# ovenboard.net
KiCad netlist of a schematic drawn in EAGLE
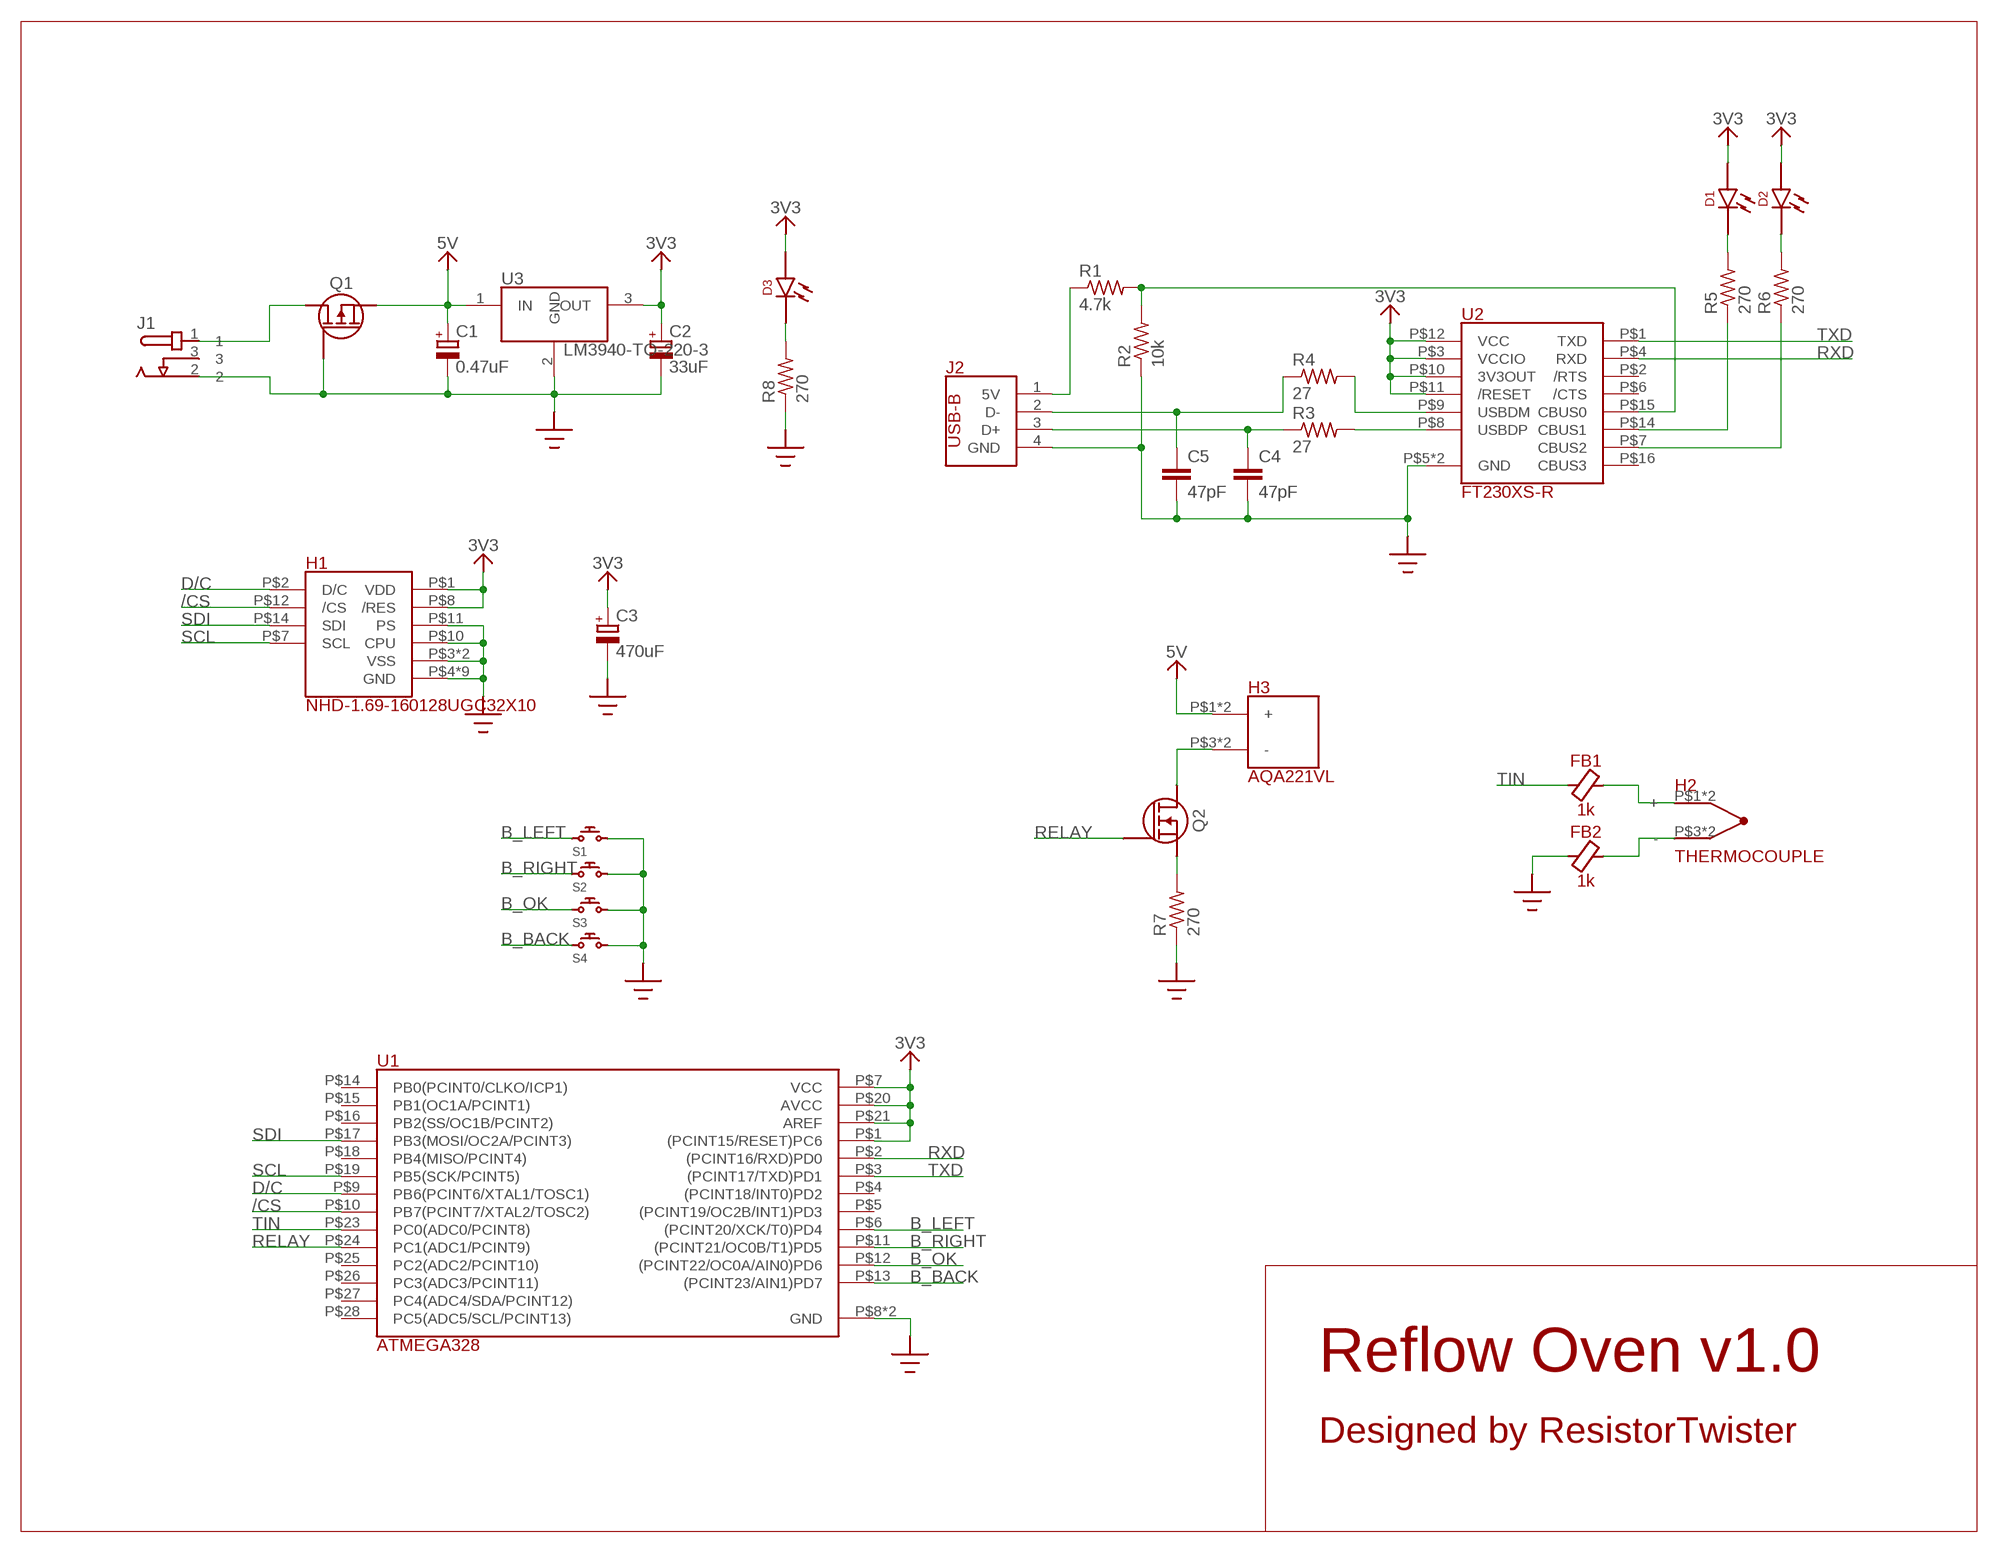
[diagram p0: schematic, sheet 1]

(export (version "E")
  (design (tool "Eeschema 10.0.6"))
  (components
    (comp (ref "C1")
      (value "0.47uF")
      (footprint "eagle-import:E5-5")
      (libsource (lib "eagle-import") (part "CPOL-EUE5-5"))
    )
    (comp (ref "C2")
      (value "33uF")
      (footprint "eagle-import:E5-5")
      (libsource (lib "eagle-import") (part "CPOL-EUE5-5"))
    )
    (comp (ref "C3")
      (value "470uF")
      (footprint "eagle-import:E5-5")
      (libsource (lib "eagle-import") (part "CPOL-EUE5-5"))
    )
    (comp (ref "C4")
      (value "47pF")
      (footprint "eagle-import:C050-024X044")
      (libsource (lib "eagle-import") (part "C-EU050-024X044"))
    )
    (comp (ref "C5")
      (value "47pF")
      (footprint "eagle-import:C050-024X044")
      (libsource (lib "eagle-import") (part "C-EU050-024X044"))
    )
    (comp (ref "D1")
      (value "LED-5")
      (footprint "eagle-import:LED5")
      (libsource (lib "eagle-import") (part "LED-5"))
    )
    (comp (ref "D2")
      (value "LED-5")
      (footprint "eagle-import:LED5")
      (libsource (lib "eagle-import") (part "LED-5"))
    )
    (comp (ref "D3")
      (value "LED-5")
      (footprint "eagle-import:LED5")
      (libsource (lib "eagle-import") (part "LED-5"))
    )
    (comp (ref "FB1")
      (value "1k")
      (footprint "eagle-import:0603")
      (libsource (lib "eagle-import") (part "FERRITE-0603"))
    )
    (comp (ref "FB2")
      (value "1k")
      (footprint "eagle-import:0603")
      (libsource (lib "eagle-import") (part "FERRITE-0603"))
    )
    (comp (ref "H1")
      (value "NHD-1.69-160128UGC32X10")
      (footprint "eagle-import:2X10HEADER0.1")
      (libsource (lib "eagle-import") (part "NHD-1.69-160128UGC32X10"))
    )
    (comp (ref "H2")
      (value "THERMOCOUPLE")
      (footprint "eagle-import:2TERMINAL")
      (libsource (lib "eagle-import") (part "THERMOCOUPLE"))
    )
    (comp (ref "H3")
      (value "AQA221VL")
      (footprint "eagle-import:2TERMINAL")
      (libsource (lib "eagle-import") (part "AQA221VL"))
    )
    (comp (ref "J1")
      (value "PJ-202B")
      (footprint "eagle-import:PJ-202B")
      (libsource (lib "eagle-import") (part "PJ-202B"))
    )
    (comp (ref "J2")
      (value "USB2.0-B1HSW6")
      (footprint "eagle-import:B1HSW6")
      (libsource (lib "eagle-import") (part "USB2.0-B1HSW6"))
    )
    (comp (ref "Q1")
      (value "MOSFET-P-TO-220-3")
      (footprint "eagle-import:TO-220-3")
      (libsource (lib "eagle-import") (part "MOSFET-P-TO-220-3"))
    )
    (comp (ref "Q2")
      (value "MOSFET-N-TO-92")
      (footprint "eagle-import:TO-92")
      (libsource (lib "eagle-import") (part "MOSFET-N-TO-92"))
    )
    (comp (ref "R1")
      (value "4.7k")
      (footprint "eagle-import:0204_5")
      (libsource (lib "eagle-import") (part "R-US_0204/5"))
    )
    (comp (ref "R2")
      (value "10k")
      (footprint "eagle-import:0204_5")
      (libsource (lib "eagle-import") (part "R-US_0204/5"))
    )
    (comp (ref "R3")
      (value "27")
      (footprint "eagle-import:0204_5")
      (libsource (lib "eagle-import") (part "R-US_0204/5"))
    )
    (comp (ref "R4")
      (value "27")
      (footprint "eagle-import:0204_5")
      (libsource (lib "eagle-import") (part "R-US_0204/5"))
    )
    (comp (ref "R5")
      (value "270")
      (footprint "eagle-import:0204_5")
      (libsource (lib "eagle-import") (part "R-US_0204/5"))
    )
    (comp (ref "R6")
      (value "270")
      (footprint "eagle-import:0204_5")
      (libsource (lib "eagle-import") (part "R-US_0204/5"))
    )
    (comp (ref "R7")
      (value "270")
      (footprint "eagle-import:0204_5")
      (libsource (lib "eagle-import") (part "R-US_0204/5"))
    )
    (comp (ref "R8")
      (value "270")
      (footprint "eagle-import:0204_5")
      (libsource (lib "eagle-import") (part "R-US_0204/5"))
    )
    (comp (ref "S1")
      (value "PUSHBUTTON")
      (footprint "eagle-import:1X2HEADER0.1")
      (libsource (lib "eagle-import") (part "PUSHBUTTON"))
    )
    (comp (ref "S2")
      (value "PUSHBUTTON")
      (footprint "eagle-import:1X2HEADER0.1")
      (libsource (lib "eagle-import") (part "PUSHBUTTON"))
    )
    (comp (ref "S3")
      (value "PUSHBUTTON")
      (footprint "eagle-import:1X2HEADER0.1")
      (libsource (lib "eagle-import") (part "PUSHBUTTON"))
    )
    (comp (ref "S4")
      (value "PUSHBUTTON")
      (footprint "eagle-import:1X2HEADER0.1")
      (libsource (lib "eagle-import") (part "PUSHBUTTON"))
    )
    (comp (ref "U1")
      (value "ATMEGA328")
      (footprint "eagle-import:28DIP0.1")
      (libsource (lib "eagle-import") (part "ATMEGA328"))
    )
    (comp (ref "U2")
      (value "FT230XS-R")
      (footprint "eagle-import:16SSOP0.025")
      (libsource (lib "eagle-import") (part "FT230XS-R"))
    )
    (comp (ref "U3")
      (value "LM3940-TO-220-3")
      (footprint "eagle-import:TO-220-3")
      (libsource (lib "eagle-import") (part "LM3940-TO-220-3"))
    )
  )
  (nets
    (net (code "1") (name "/B_BACK") (class "Default")
      (node (ref "S4") (pin "2") (pinfunction "2_2") (pintype "passive"))
      (node (ref "U1") (pin "P$13") (pinfunction "(PCINT23/AIN1)PD7_P$13") (pintype "bidirectional"))
    )
    (net (code "2") (name "/B_LEFT") (class "Default")
      (node (ref "S1") (pin "2") (pinfunction "2_2") (pintype "passive"))
      (node (ref "U1") (pin "P$6") (pinfunction "(PCINT20/XCK/T0)PD4_P$6") (pintype "bidirectional"))
    )
    (net (code "3") (name "/B_OK") (class "Default")
      (node (ref "S3") (pin "2") (pinfunction "2_2") (pintype "passive"))
      (node (ref "U1") (pin "P$12") (pinfunction "(PCINT22/OC0A/AIN0)PD6_P$12") (pintype "bidirectional"))
    )
    (net (code "4") (name "/B_RIGHT") (class "Default")
      (node (ref "S2") (pin "2") (pinfunction "2_2") (pintype "passive"))
      (node (ref "U1") (pin "P$11") (pinfunction "(PCINT21/OC0B/T1)PD5_P$11") (pintype "bidirectional"))
    )
    (net (code "5") (name "/D{slash}C") (class "Default")
      (node (ref "H1") (pin "P$2") (pinfunction "D/C_P$2") (pintype "bidirectional"))
      (node (ref "U1") (pin "P$9") (pinfunction "PB6(PCINT6/XTAL1/TOSC1)_P$9") (pintype "bidirectional"))
    )
    (net (code "6") (name "/RELAY") (class "Default")
      (node (ref "Q2") (pin "2") (pinfunction "G_2") (pintype "bidirectional"))
      (node (ref "U1") (pin "P$24") (pinfunction "PC1(ADC1/PCINT9)_P$24") (pintype "bidirectional"))
    )
    (net (code "7") (name "/RXD") (class "Default")
      (node (ref "U1") (pin "P$2") (pinfunction "(PCINT16/RXD)PD0_P$2") (pintype "bidirectional"))
      (node (ref "U2") (pin "P$4") (pinfunction "RXD_P$4") (pintype "bidirectional"))
    )
    (net (code "8") (name "/SCL") (class "Default")
      (node (ref "H1") (pin "P$7") (pinfunction "SCL_P$7") (pintype "bidirectional"))
      (node (ref "U1") (pin "P$19") (pinfunction "PB5(SCK/PCINT5)_P$19") (pintype "bidirectional"))
    )
    (net (code "9") (name "/SDI") (class "Default")
      (node (ref "H1") (pin "P$14") (pinfunction "SDI_P$14") (pintype "bidirectional"))
      (node (ref "U1") (pin "P$17") (pinfunction "PB3(MOSI/OC2A/PCINT3)_P$17") (pintype "bidirectional"))
    )
    (net (code "10") (name "/TIN") (class "Default")
      (node (ref "FB1") (pin "1") (pinfunction "1_1") (pintype "passive"))
      (node (ref "U1") (pin "P$23") (pinfunction "PC0(ADC0/PCINT8)_P$23") (pintype "bidirectional"))
    )
    (net (code "11") (name "/TXD") (class "Default")
      (node (ref "U1") (pin "P$3") (pinfunction "(PCINT17/TXD)PD1_P$3") (pintype "bidirectional"))
      (node (ref "U2") (pin "P$1") (pinfunction "TXD_P$1") (pintype "bidirectional"))
    )
    (net (code "12") (name "/{slash}CS") (class "Default")
      (node (ref "H1") (pin "P$12") (pinfunction "/CS_P$12") (pintype "bidirectional"))
      (node (ref "U1") (pin "P$10") (pinfunction "PB7(PCINT7/XTAL2/TOSC2)_P$10") (pintype "bidirectional"))
    )
    (net (code "13") (name "3V3") (class "Default")
      (node (ref "C2") (pin "+") (pinfunction "+_+") (pintype "passive"))
      (node (ref "C3") (pin "+") (pinfunction "+_+") (pintype "passive"))
      (node (ref "D1") (pin "A") (pinfunction "A_A") (pintype "bidirectional"))
      (node (ref "D2") (pin "A") (pinfunction "A_A") (pintype "bidirectional"))
      (node (ref "D3") (pin "A") (pinfunction "A_A") (pintype "bidirectional"))
      (node (ref "H1") (pin "P$1") (pinfunction "VDD_P$1") (pintype "bidirectional"))
      (node (ref "H1") (pin "P$8") (pinfunction "/RES_P$8") (pintype "bidirectional"))
      (node (ref "U1") (pin "P$1") (pinfunction "(PCINT15/RESET)PC6_P$1") (pintype "bidirectional"))
      (node (ref "U1") (pin "P$20") (pinfunction "AVCC_P$20") (pintype "bidirectional"))
      (node (ref "U1") (pin "P$21") (pinfunction "AREF_P$21") (pintype "bidirectional"))
      (node (ref "U1") (pin "P$7") (pinfunction "VCC_P$7") (pintype "bidirectional"))
      (node (ref "U2") (pin "P$10") (pinfunction "3V3OUT_P$10") (pintype "bidirectional"))
      (node (ref "U2") (pin "P$11") (pinfunction "/RESET_P$11") (pintype "bidirectional"))
      (node (ref "U2") (pin "P$12") (pinfunction "VCC_P$12") (pintype "bidirectional"))
      (node (ref "U2") (pin "P$3") (pinfunction "VCCIO_P$3") (pintype "bidirectional"))
      (node (ref "U3") (pin "3") (pinfunction "OUT_3") (pintype "bidirectional"))
    )
    (net (code "14") (name "5V") (class "Default")
      (node (ref "C1") (pin "+") (pinfunction "+_+") (pintype "passive"))
      (node (ref "H3") (pin "P$1") (pinfunction "+_P$1") (pintype "bidirectional"))
      (node (ref "H3") (pin "P$2") (pinfunction "+_P$2") (pintype "bidirectional"))
      (node (ref "Q1") (pin "2") (pinfunction "S_2") (pintype "bidirectional"))
      (node (ref "U3") (pin "1") (pinfunction "IN_1") (pintype "bidirectional"))
    )
    (net (code "15") (name "GND") (class "Default")
      (node (ref "C1") (pin "-") (pinfunction "-_-") (pintype "passive"))
      (node (ref "C2") (pin "-") (pinfunction "-_-") (pintype "passive"))
      (node (ref "C3") (pin "-") (pinfunction "-_-") (pintype "passive"))
      (node (ref "C4") (pin "2") (pinfunction "2_2") (pintype "passive"))
      (node (ref "C5") (pin "2") (pinfunction "2_2") (pintype "passive"))
      (node (ref "FB2") (pin "1") (pinfunction "1_1") (pintype "passive"))
      (node (ref "H1") (pin "P$10") (pinfunction "CPU_P$10") (pintype "bidirectional"))
      (node (ref "H1") (pin "P$11") (pinfunction "PS_P$11") (pintype "bidirectional"))
      (node (ref "H1") (pin "P$13") (pinfunction "GND_P$13") (pintype "bidirectional"))
      (node (ref "H1") (pin "P$15") (pinfunction "GND_P$15") (pintype "bidirectional"))
      (node (ref "H1") (pin "P$16") (pinfunction "GND_P$16") (pintype "bidirectional"))
      (node (ref "H1") (pin "P$17") (pinfunction "GND_P$17") (pintype "bidirectional"))
      (node (ref "H1") (pin "P$18") (pinfunction "VSS_P$18") (pintype "bidirectional"))
      (node (ref "H1") (pin "P$20") (pinfunction "GND_P$20") (pintype "bidirectional"))
      (node (ref "H1") (pin "P$3") (pinfunction "VSS_P$3") (pintype "bidirectional"))
      (node (ref "H1") (pin "P$4") (pinfunction "GND_P$4") (pintype "bidirectional"))
      (node (ref "H1") (pin "P$5") (pinfunction "GND_P$5") (pintype "bidirectional"))
      (node (ref "H1") (pin "P$6") (pinfunction "GND_P$6") (pintype "bidirectional"))
      (node (ref "H1") (pin "P$9") (pinfunction "GND_P$9") (pintype "bidirectional"))
      (node (ref "J1") (pin "2") (pinfunction "2_2") (pintype "bidirectional"))
      (node (ref "J2") (pin "4") (pinfunction "GND_4") (pintype "bidirectional"))
      (node (ref "Q1") (pin "1") (pinfunction "G_1") (pintype "bidirectional"))
      (node (ref "R2") (pin "1") (pinfunction "1_1") (pintype "passive"))
      (node (ref "R7") (pin "1") (pinfunction "1_1") (pintype "passive"))
      (node (ref "R8") (pin "1") (pinfunction "1_1") (pintype "passive"))
      (node (ref "S1") (pin "1") (pinfunction "1_1") (pintype "passive"))
      (node (ref "S2") (pin "1") (pinfunction "1_1") (pintype "passive"))
      (node (ref "S3") (pin "1") (pinfunction "1_1") (pintype "passive"))
      (node (ref "S4") (pin "1") (pinfunction "1_1") (pintype "passive"))
      (node (ref "U1") (pin "P$22") (pinfunction "GND_P$22") (pintype "bidirectional"))
      (node (ref "U1") (pin "P$8") (pinfunction "GND_P$8") (pintype "bidirectional"))
      (node (ref "U2") (pin "P$13") (pinfunction "GND_P$13") (pintype "bidirectional"))
      (node (ref "U2") (pin "P$5") (pinfunction "GND_P$5") (pintype "bidirectional"))
      (node (ref "U3") (pin "2") (pinfunction "GND_2") (pintype "bidirectional"))
    )
    (net (code "16") (name "Net-(D1-PadC)") (class "Default")
      (node (ref "D1") (pin "C") (pinfunction "C_C") (pintype "bidirectional"))
      (node (ref "R5") (pin "2") (pinfunction "2_2") (pintype "passive"))
    )
    (net (code "17") (name "Net-(D2-PadC)") (class "Default")
      (node (ref "D2") (pin "C") (pinfunction "C_C") (pintype "bidirectional"))
      (node (ref "R6") (pin "2") (pinfunction "2_2") (pintype "passive"))
    )
    (net (code "18") (name "Net-(D3-PadC)") (class "Default")
      (node (ref "D3") (pin "C") (pinfunction "C_C") (pintype "bidirectional"))
      (node (ref "R8") (pin "2") (pinfunction "2_2") (pintype "passive"))
    )
    (net (code "19") (name "Net-(FB1-Pad2)") (class "Default")
      (node (ref "FB1") (pin "2") (pinfunction "2_2") (pintype "passive"))
      (node (ref "H2") (pin "P$1") (pinfunction "+_P$1") (pintype "bidirectional"))
      (node (ref "H2") (pin "P$2") (pinfunction "+_P$2") (pintype "bidirectional"))
    )
    (net (code "20") (name "Net-(FB2-Pad2)") (class "Default")
      (node (ref "FB2") (pin "2") (pinfunction "2_2") (pintype "passive"))
      (node (ref "H2") (pin "P$3") (pinfunction "-_P$3") (pintype "bidirectional"))
      (node (ref "H2") (pin "P$4") (pinfunction "-_P$4") (pintype "bidirectional"))
    )
    (net (code "21") (name "Net-(J2-5V)") (class "Default")
      (node (ref "J2") (pin "1") (pinfunction "5V_1") (pintype "bidirectional"))
      (node (ref "R1") (pin "1") (pinfunction "1_1") (pintype "passive"))
    )
    (net (code "22") (name "Net-(J2-D+)") (class "Default")
      (node (ref "C4") (pin "1") (pinfunction "1_1") (pintype "passive"))
      (node (ref "J2") (pin "3") (pinfunction "D+_3") (pintype "bidirectional"))
      (node (ref "R3") (pin "1") (pinfunction "1_1") (pintype "passive"))
    )
    (net (code "23") (name "Net-(J2-D-)") (class "Default")
      (node (ref "C5") (pin "1") (pinfunction "1_1") (pintype "passive"))
      (node (ref "J2") (pin "2") (pinfunction "D-_2") (pintype "bidirectional"))
      (node (ref "R4") (pin "1") (pinfunction "1_1") (pintype "passive"))
    )
    (net (code "24") (name "Net-(Q1-D)") (class "Default")
      (node (ref "J1") (pin "1") (pinfunction "1_1") (pintype "bidirectional"))
      (node (ref "Q1") (pin "3") (pinfunction "D_3") (pintype "bidirectional"))
    )
    (net (code "25") (name "Net-(Q2-D)") (class "Default")
      (node (ref "H3") (pin "P$3") (pinfunction "-_P$3") (pintype "bidirectional"))
      (node (ref "H3") (pin "P$4") (pinfunction "-_P$4") (pintype "bidirectional"))
      (node (ref "Q2") (pin "3") (pinfunction "D_3") (pintype "bidirectional"))
    )
    (net (code "26") (name "Net-(Q2-S)") (class "Default")
      (node (ref "Q2") (pin "1") (pinfunction "S_1") (pintype "bidirectional"))
      (node (ref "R7") (pin "2") (pinfunction "2_2") (pintype "passive"))
    )
    (net (code "27") (name "Net-(U2-CBUS0)") (class "Default")
      (node (ref "R1") (pin "2") (pinfunction "2_2") (pintype "passive"))
      (node (ref "R2") (pin "2") (pinfunction "2_2") (pintype "passive"))
      (node (ref "U2") (pin "P$15") (pinfunction "CBUS0_P$15") (pintype "bidirectional"))
    )
    (net (code "28") (name "Net-(U2-CBUS1)") (class "Default")
      (node (ref "R5") (pin "1") (pinfunction "1_1") (pintype "passive"))
      (node (ref "U2") (pin "P$14") (pinfunction "CBUS1_P$14") (pintype "bidirectional"))
    )
    (net (code "29") (name "Net-(U2-CBUS2)") (class "Default")
      (node (ref "R6") (pin "1") (pinfunction "1_1") (pintype "passive"))
      (node (ref "U2") (pin "P$7") (pinfunction "CBUS2_P$7") (pintype "bidirectional"))
    )
    (net (code "30") (name "Net-(U2-USBDM)") (class "Default")
      (node (ref "R4") (pin "2") (pinfunction "2_2") (pintype "passive"))
      (node (ref "U2") (pin "P$9") (pinfunction "USBDM_P$9") (pintype "bidirectional"))
    )
    (net (code "31") (name "Net-(U2-USBDP)") (class "Default")
      (node (ref "R3") (pin "2") (pinfunction "2_2") (pintype "passive"))
      (node (ref "U2") (pin "P$8") (pinfunction "USBDP_P$8") (pintype "bidirectional"))
    )
    (net (code "32") (name "unconnected-(J1-Pad3)") (class "Default")
      (node (ref "J1") (pin "3") (pinfunction "3_3") (pintype "bidirectional"))
    )
    (net (code "33") (name "unconnected-(U1-(PCINT18{slash}INT0)PD2-PadP$4)") (class "Default")
      (node (ref "U1") (pin "P$4") (pinfunction "(PCINT18/INT0)PD2_P$4") (pintype "bidirectional"))
    )
    (net (code "34") (name "unconnected-(U1-(PCINT19{slash}OC2B{slash}INT1)PD3-PadP$5)") (class "Default")
      (node (ref "U1") (pin "P$5") (pinfunction "(PCINT19/OC2B/INT1)PD3_P$5") (pintype "bidirectional"))
    )
    (net (code "35") (name "unconnected-(U1-PB0(PCINT0{slash}CLKO{slash}ICP1)-PadP$14)") (class "Default")
      (node (ref "U1") (pin "P$14") (pinfunction "PB0(PCINT0/CLKO/ICP1)_P$14") (pintype "bidirectional"))
    )
    (net (code "36") (name "unconnected-(U1-PB1(OC1A{slash}PCINT1)-PadP$15)") (class "Default")
      (node (ref "U1") (pin "P$15") (pinfunction "PB1(OC1A/PCINT1)_P$15") (pintype "bidirectional"))
    )
    (net (code "37") (name "unconnected-(U1-PB2(SS{slash}OC1B{slash}PCINT2)-PadP$16)") (class "Default")
      (node (ref "U1") (pin "P$16") (pinfunction "PB2(SS/OC1B/PCINT2)_P$16") (pintype "bidirectional"))
    )
    (net (code "38") (name "unconnected-(U1-PB4(MISO{slash}PCINT4)-PadP$18)") (class "Default")
      (node (ref "U1") (pin "P$18") (pinfunction "PB4(MISO/PCINT4)_P$18") (pintype "bidirectional"))
    )
    (net (code "39") (name "unconnected-(U1-PC2(ADC2{slash}PCINT10)-PadP$25)") (class "Default")
      (node (ref "U1") (pin "P$25") (pinfunction "PC2(ADC2/PCINT10)_P$25") (pintype "bidirectional"))
    )
    (net (code "40") (name "unconnected-(U1-PC3(ADC3{slash}PCINT11)-PadP$26)") (class "Default")
      (node (ref "U1") (pin "P$26") (pinfunction "PC3(ADC3/PCINT11)_P$26") (pintype "bidirectional"))
    )
    (net (code "41") (name "unconnected-(U1-PC4(ADC4{slash}SDA{slash}PCINT12)-PadP$27)") (class "Default")
      (node (ref "U1") (pin "P$27") (pinfunction "PC4(ADC4/SDA/PCINT12)_P$27") (pintype "bidirectional"))
    )
    (net (code "42") (name "unconnected-(U1-PC5(ADC5{slash}SCL{slash}PCINT13)-PadP$28)") (class "Default")
      (node (ref "U1") (pin "P$28") (pinfunction "PC5(ADC5/SCL/PCINT13)_P$28") (pintype "bidirectional"))
    )
    (net (code "43") (name "unconnected-(U2-CBUS3-PadP$16)") (class "Default")
      (node (ref "U2") (pin "P$16") (pinfunction "CBUS3_P$16") (pintype "bidirectional"))
    )
    (net (code "44") (name "unconnected-(U2-{slash}CTS-PadP$6)") (class "Default")
      (node (ref "U2") (pin "P$6") (pinfunction "/CTS_P$6") (pintype "bidirectional"))
    )
    (net (code "45") (name "unconnected-(U2-{slash}RTS-PadP$2)") (class "Default")
      (node (ref "U2") (pin "P$2") (pinfunction "/RTS_P$2") (pintype "bidirectional"))
    )
  )
)
